# Braille_drive.net
KiCad netlist of a schematic drawn in EAGLE
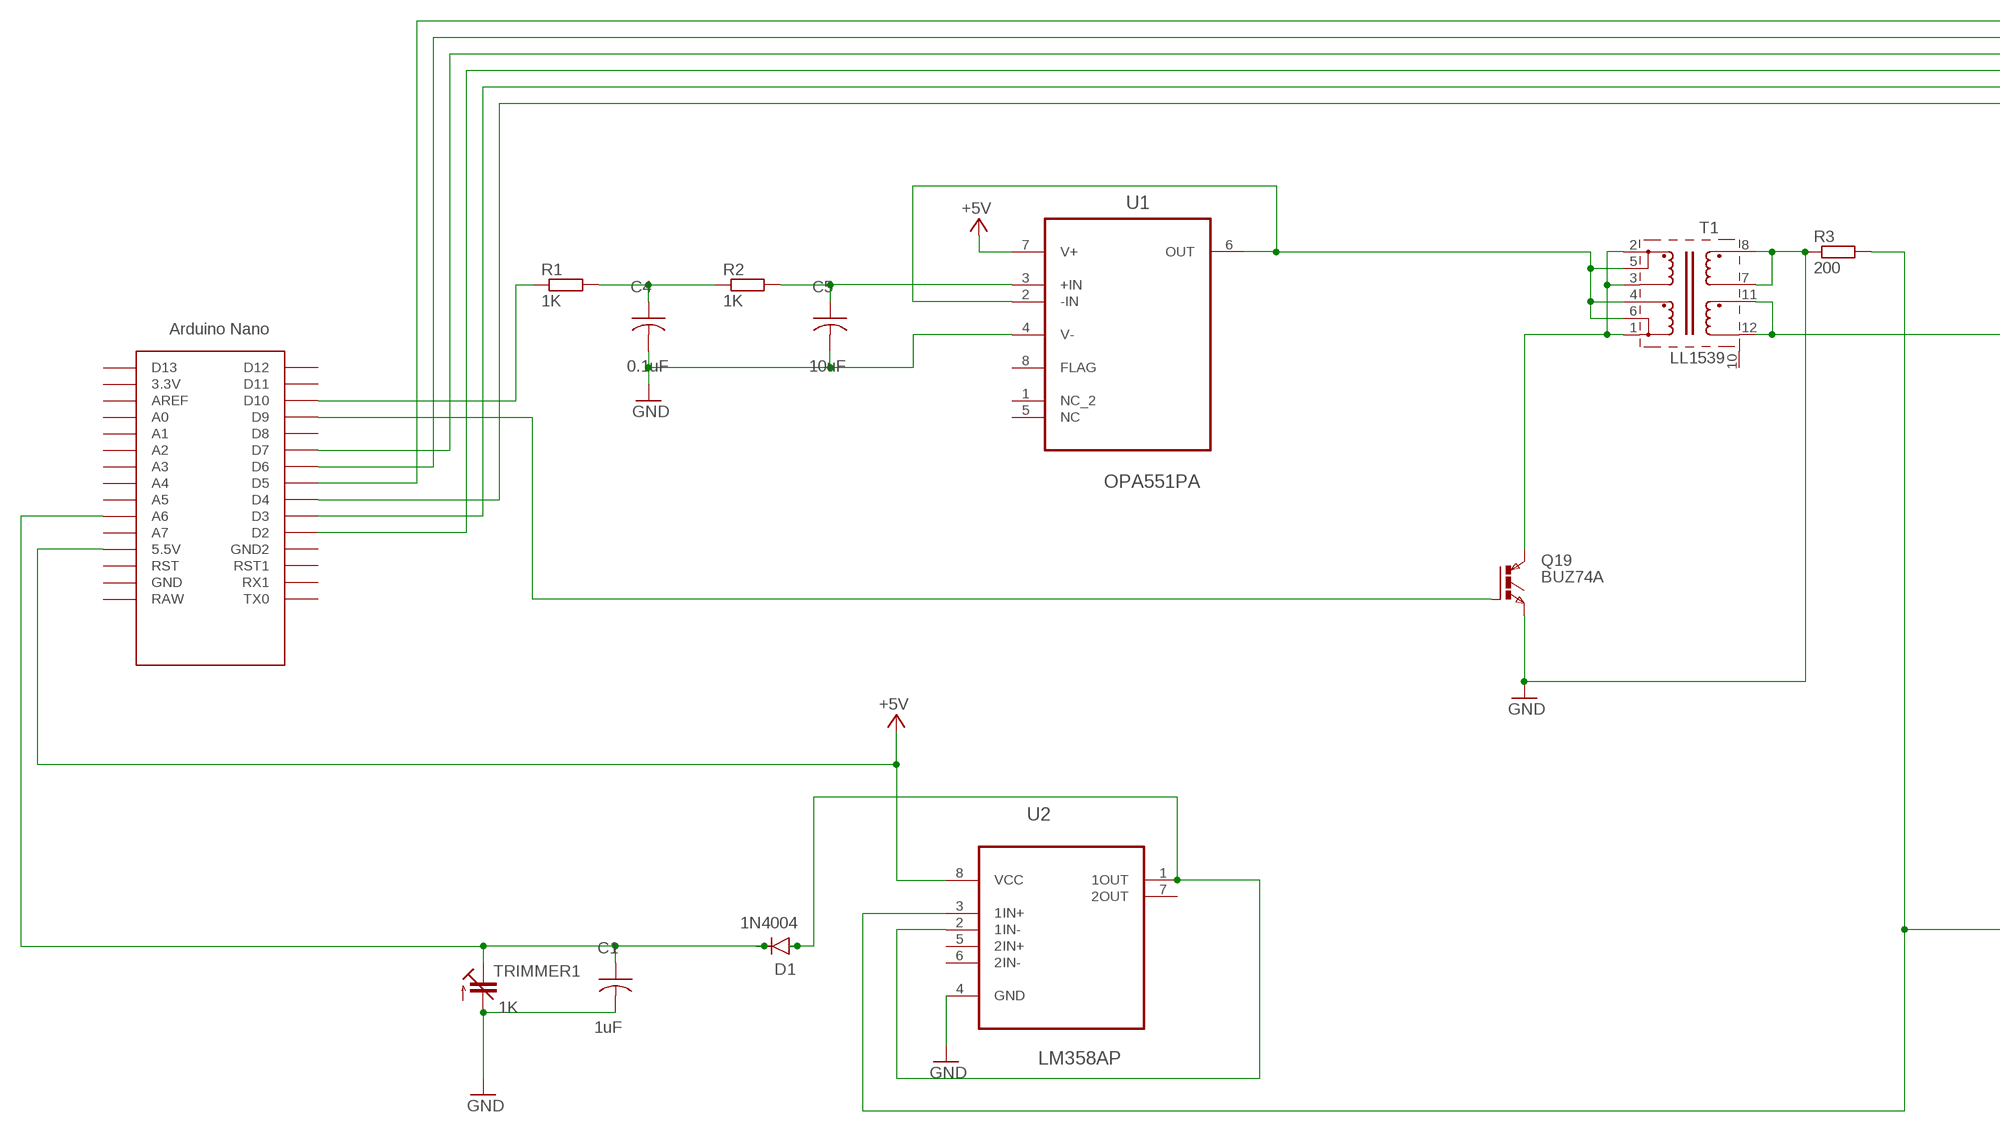
[diagram p0: schematic, sheet 1, part 1 of 2]
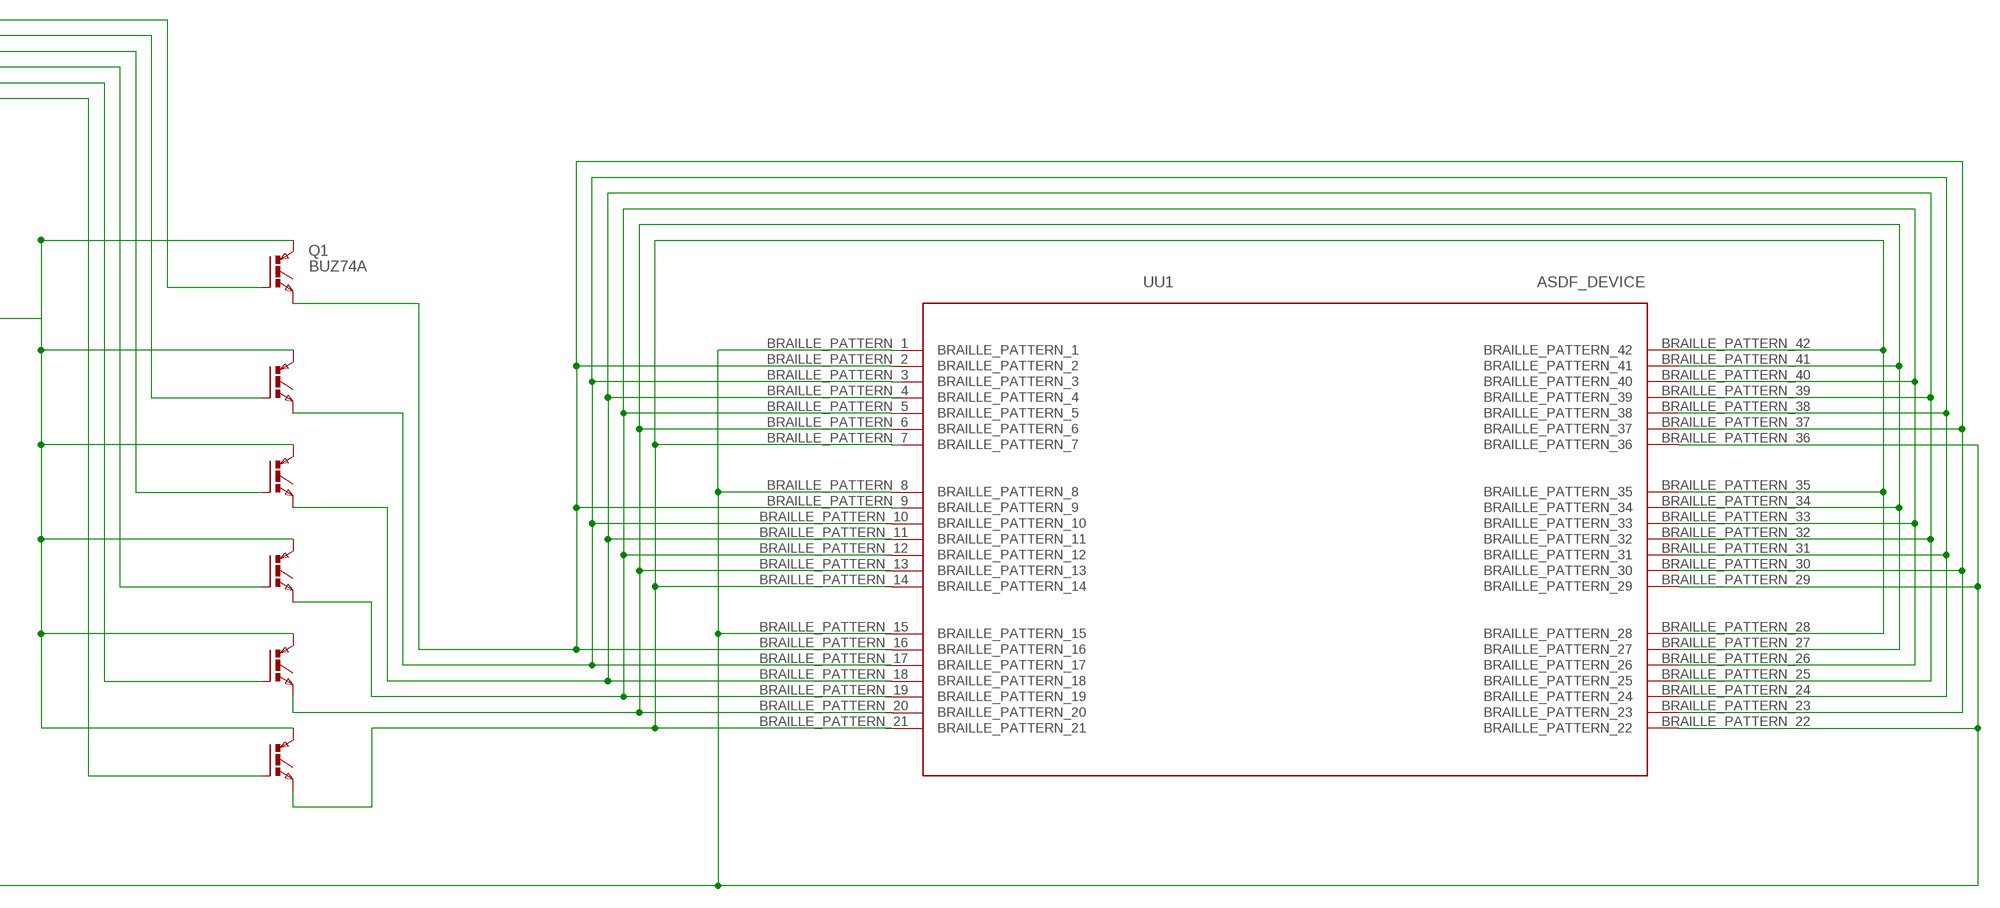
[diagram p1: schematic, sheet 1, part 2 of 2]

(export (version "E")
  (design (tool "Eeschema 10.0.6"))
  (components
    (comp (ref "C1")
      (value "1uF")
      (footprint "eagle-import:CAP_RADIAL_2MM")
      (fields
        (field (name "DIGIKEY_PART_NUMBER") "P5178-ND")
        (field (name "MANUFACTURER") "Panasonic Electronic Components")
        (field (name "MPN") "ECA-1HM100")
        (field (name "CREATED_BY") "PCBLayout.com")
      )
      (libsource (lib "eagle-import") (part "ECA-1HM100"))
    )
    (comp (ref "C4")
      (value "0.1uF")
      (footprint "eagle-import:CAP_RADIAL_2MM")
      (fields
        (field (name "DIGIKEY_PART_NUMBER") "P5178-ND")
        (field (name "MANUFACTURER") "Panasonic Electronic Components")
        (field (name "MPN") "ECA-1HM100")
        (field (name "CREATED_BY") "PCBLayout.com")
      )
      (libsource (lib "eagle-import") (part "ECA-1HM100"))
    )
    (comp (ref "C5")
      (value "10uF")
      (footprint "eagle-import:CAP_RADIAL_2MM")
      (fields
        (field (name "DIGIKEY_PART_NUMBER") "P5178-ND")
        (field (name "MANUFACTURER") "Panasonic Electronic Components")
        (field (name "MPN") "ECA-1HM100")
        (field (name "CREATED_BY") "PCBLayout.com")
      )
      (libsource (lib "eagle-import") (part "ECA-1HM100"))
    )
    (comp (ref "D1")
      (value "1N4004")
      (footprint "eagle-import:DO-41")
      (fields
        (field (name "DIGIKEY_PART_NUMBER") "1N4004MSCT-ND")
        (field (name "MANUFACTURER") "Micro Commercial Co")
        (field (name "CREATED_BY") "PCBLayout.com")
      )
      (libsource (lib "eagle-import") (part "1N4004"))
    )
    (comp (ref "Q1")
      (value "BUZ74A")
      (footprint "eagle-import:TO220AV")
      (libsource (lib "eagle-import") (part "IGBTTO220AV"))
    )
    (comp (ref "Q2")
      (value "BUZ74A")
      (footprint "eagle-import:TO220AV")
      (libsource (lib "eagle-import") (part "IGBTTO220AV"))
    )
    (comp (ref "Q3")
      (value "BUZ74A")
      (footprint "eagle-import:TO220AV")
      (libsource (lib "eagle-import") (part "IGBTTO220AV"))
    )
    (comp (ref "Q4")
      (value "BUZ74A")
      (footprint "eagle-import:TO220AV")
      (libsource (lib "eagle-import") (part "IGBTTO220AV"))
    )
    (comp (ref "Q5")
      (value "BUZ74A")
      (footprint "eagle-import:TO220AV")
      (libsource (lib "eagle-import") (part "IGBTTO220AV"))
    )
    (comp (ref "Q6")
      (value "BUZ74A")
      (footprint "eagle-import:TO220AV")
      (libsource (lib "eagle-import") (part "IGBTTO220AV"))
    )
    (comp (ref "Q19")
      (value "BUZ74A")
      (footprint "eagle-import:TO220AV")
      (libsource (lib "eagle-import") (part "IGBTTO220AV"))
    )
    (comp (ref "R1")
      (value "1K")
      (footprint "eagle-import:0204V")
      (libsource (lib "eagle-import") (part "R-EU_0204/2V"))
    )
    (comp (ref "R2")
      (value "1K")
      (footprint "eagle-import:0204V")
      (libsource (lib "eagle-import") (part "R-EU_0204/2V"))
    )
    (comp (ref "R3")
      (value "200")
      (footprint "eagle-import:0204V")
      (libsource (lib "eagle-import") (part "R-EU_0204/2V"))
    )
    (comp (ref "T1")
      (value "LL1539")
      (footprint "eagle-import:LL1539")
      (libsource (lib "eagle-import") (part "LL1539"))
    )
    (comp (ref "TRIMMER1")
      (value "1K")
      (footprint "eagle-import:CTRIM3040.452")
      (libsource (lib "eagle-import") (part "C-TRIMM3040.452"))
    )
    (comp (ref "U$1")
      (value "NANO")
      (footprint "eagle-import:NANO")
      (libsource (lib "eagle-import") (part "NANO"))
    )
    (comp (ref "U1")
      (value "OPA551PA")
      (footprint "eagle-import:DIP254P762X508-8")
      (libsource (lib "eagle-import") (part "OPA551PA"))
    )
    (comp (ref "U2")
      (value "LM358AP")
      (footprint "eagle-import:DIP254P762X508-8")
      (libsource (lib "eagle-import") (part "LM358AP"))
    )
    (comp (ref "UU1")
      (value "ASDF_DEVICE")
      (footprint "eagle-import:BRAILLE_PATTERN1")
      (libsource (lib "eagle-import") (part "ASDF_DEVICE"))
    )
  )
  (nets
    (net (code "1") (name "+5V") (class "Default")
      (node (ref "U$1") (pin "5V") (pinfunction "5.5V_5V") (pintype "bidirectional"))
      (node (ref "U1") (pin "7") (pinfunction "V+_7") (pintype "power_in"))
      (node (ref "U2") (pin "8") (pinfunction "VCC_8") (pintype "power_in"))
    )
    (net (code "2") (name "GND") (class "Default")
      (node (ref "C1") (pin "2") (pinfunction "2_2") (pintype "passive"))
      (node (ref "C4") (pin "2") (pinfunction "2_2") (pintype "passive"))
      (node (ref "C5") (pin "2") (pinfunction "2_2") (pintype "passive"))
      (node (ref "Q19") (pin "E") (pinfunction "E_E") (pintype "passive"))
      (node (ref "R3") (pin "1") (pinfunction "1_1") (pintype "passive"))
      (node (ref "T1") (pin "7") (pinfunction "7_7") (pintype "passive"))
      (node (ref "T1") (pin "8") (pinfunction "8_8") (pintype "passive"))
      (node (ref "TRIMMER1") (pin "2") (pinfunction "A_2") (pintype "passive"))
      (node (ref "U1") (pin "4") (pinfunction "V-_4") (pintype "power_in"))
      (node (ref "U2") (pin "4") (pinfunction "GND_4") (pintype "passive"))
    )
    (net (code "3") (name "Net-(C4-Pad1)") (class "Default")
      (node (ref "C4") (pin "1") (pinfunction "1_1") (pintype "passive"))
      (node (ref "R1") (pin "2") (pinfunction "2_2") (pintype "passive"))
      (node (ref "R2") (pin "1") (pinfunction "1_1") (pintype "passive"))
    )
    (net (code "4") (name "Net-(Q1-PadC)") (class "Default")
      (node (ref "Q1") (pin "C") (pinfunction "C_C") (pintype "passive"))
      (node (ref "Q2") (pin "C") (pinfunction "C_C") (pintype "passive"))
      (node (ref "Q3") (pin "C") (pinfunction "C_C") (pintype "passive"))
      (node (ref "Q4") (pin "C") (pinfunction "C_C") (pintype "passive"))
      (node (ref "Q5") (pin "C") (pinfunction "C_C") (pintype "passive"))
      (node (ref "Q6") (pin "C") (pinfunction "C_C") (pintype "passive"))
      (node (ref "T1") (pin "11") (pinfunction "11_11") (pintype "passive"))
      (node (ref "T1") (pin "12") (pinfunction "12_12") (pintype "passive"))
    )
    (net (code "5") (name "Net-(Q1-PadE)") (class "Default")
      (node (ref "Q1") (pin "E") (pinfunction "E_E") (pintype "passive"))
      (node (ref "UU1") (pin "BRAILLE_PATTERN_16") (pinfunction "BRAILLE_PATTERN_16_BRAILLE_PATTERN_16") (pintype "bidirectional"))
      (node (ref "UU1") (pin "BRAILLE_PATTERN_2") (pinfunction "BRAILLE_PATTERN_2_BRAILLE_PATTERN_2") (pintype "bidirectional"))
      (node (ref "UU1") (pin "BRAILLE_PATTERN_23") (pinfunction "BRAILLE_PATTERN_23_BRAILLE_PATTERN_23") (pintype "bidirectional"))
      (node (ref "UU1") (pin "BRAILLE_PATTERN_30") (pinfunction "BRAILLE_PATTERN_30_BRAILLE_PATTERN_30") (pintype "bidirectional"))
      (node (ref "UU1") (pin "BRAILLE_PATTERN_37") (pinfunction "BRAILLE_PATTERN_37_BRAILLE_PATTERN_37") (pintype "bidirectional"))
      (node (ref "UU1") (pin "BRAILLE_PATTERN_9") (pinfunction "BRAILLE_PATTERN_9_BRAILLE_PATTERN_9") (pintype "bidirectional"))
    )
    (net (code "6") (name "Net-(Q1-PadG)") (class "Default")
      (node (ref "Q1") (pin "G") (pinfunction "G_G") (pintype "passive"))
      (node (ref "U$1") (pin "D5") (pinfunction "D5_D5") (pintype "bidirectional"))
    )
    (net (code "7") (name "Net-(Q2-PadE)") (class "Default")
      (node (ref "Q2") (pin "E") (pinfunction "E_E") (pintype "passive"))
      (node (ref "UU1") (pin "BRAILLE_PATTERN_10") (pinfunction "BRAILLE_PATTERN_10_BRAILLE_PATTERN_10") (pintype "bidirectional"))
      (node (ref "UU1") (pin "BRAILLE_PATTERN_17") (pinfunction "BRAILLE_PATTERN_17_BRAILLE_PATTERN_17") (pintype "bidirectional"))
      (node (ref "UU1") (pin "BRAILLE_PATTERN_24") (pinfunction "BRAILLE_PATTERN_24_BRAILLE_PATTERN_24") (pintype "bidirectional"))
      (node (ref "UU1") (pin "BRAILLE_PATTERN_3") (pinfunction "BRAILLE_PATTERN_3_BRAILLE_PATTERN_3") (pintype "bidirectional"))
      (node (ref "UU1") (pin "BRAILLE_PATTERN_31") (pinfunction "BRAILLE_PATTERN_31_BRAILLE_PATTERN_31") (pintype "bidirectional"))
      (node (ref "UU1") (pin "BRAILLE_PATTERN_38") (pinfunction "BRAILLE_PATTERN_38_BRAILLE_PATTERN_38") (pintype "bidirectional"))
    )
    (net (code "8") (name "Net-(Q2-PadG)") (class "Default")
      (node (ref "Q2") (pin "G") (pinfunction "G_G") (pintype "passive"))
      (node (ref "U$1") (pin "D6") (pinfunction "D6_D6") (pintype "bidirectional"))
    )
    (net (code "9") (name "Net-(Q3-PadE)") (class "Default")
      (node (ref "Q3") (pin "E") (pinfunction "E_E") (pintype "passive"))
      (node (ref "UU1") (pin "BRAILLE_PATTERN_11") (pinfunction "BRAILLE_PATTERN_11_BRAILLE_PATTERN_11") (pintype "bidirectional"))
      (node (ref "UU1") (pin "BRAILLE_PATTERN_18") (pinfunction "BRAILLE_PATTERN_18_BRAILLE_PATTERN_18") (pintype "bidirectional"))
      (node (ref "UU1") (pin "BRAILLE_PATTERN_25") (pinfunction "BRAILLE_PATTERN_25_BRAILLE_PATTERN_25") (pintype "bidirectional"))
      (node (ref "UU1") (pin "BRAILLE_PATTERN_32") (pinfunction "BRAILLE_PATTERN_32_BRAILLE_PATTERN_32") (pintype "bidirectional"))
      (node (ref "UU1") (pin "BRAILLE_PATTERN_39") (pinfunction "BRAILLE_PATTERN_39_BRAILLE_PATTERN_39") (pintype "bidirectional"))
      (node (ref "UU1") (pin "BRAILLE_PATTERN_4") (pinfunction "BRAILLE_PATTERN_4_BRAILLE_PATTERN_4") (pintype "bidirectional"))
    )
    (net (code "10") (name "Net-(Q3-PadG)") (class "Default")
      (node (ref "Q3") (pin "G") (pinfunction "G_G") (pintype "passive"))
      (node (ref "U$1") (pin "D7") (pinfunction "D7_D7") (pintype "bidirectional"))
    )
    (net (code "11") (name "Net-(Q4-PadE)") (class "Default")
      (node (ref "Q4") (pin "E") (pinfunction "E_E") (pintype "passive"))
      (node (ref "UU1") (pin "BRAILLE_PATTERN_12") (pinfunction "BRAILLE_PATTERN_12_BRAILLE_PATTERN_12") (pintype "bidirectional"))
      (node (ref "UU1") (pin "BRAILLE_PATTERN_19") (pinfunction "BRAILLE_PATTERN_19_BRAILLE_PATTERN_19") (pintype "bidirectional"))
      (node (ref "UU1") (pin "BRAILLE_PATTERN_26") (pinfunction "BRAILLE_PATTERN_26_BRAILLE_PATTERN_26") (pintype "bidirectional"))
      (node (ref "UU1") (pin "BRAILLE_PATTERN_33") (pinfunction "BRAILLE_PATTERN_33_BRAILLE_PATTERN_33") (pintype "bidirectional"))
      (node (ref "UU1") (pin "BRAILLE_PATTERN_40") (pinfunction "BRAILLE_PATTERN_40_BRAILLE_PATTERN_40") (pintype "bidirectional"))
      (node (ref "UU1") (pin "BRAILLE_PATTERN_5") (pinfunction "BRAILLE_PATTERN_5_BRAILLE_PATTERN_5") (pintype "bidirectional"))
    )
    (net (code "12") (name "Net-(Q4-PadG)") (class "Default")
      (node (ref "Q4") (pin "G") (pinfunction "G_G") (pintype "passive"))
      (node (ref "U$1") (pin "D2") (pinfunction "D2_D2") (pintype "bidirectional"))
    )
    (net (code "13") (name "Net-(Q5-PadE)") (class "Default")
      (node (ref "Q5") (pin "E") (pinfunction "E_E") (pintype "passive"))
      (node (ref "UU1") (pin "BRAILLE_PATTERN_13") (pinfunction "BRAILLE_PATTERN_13_BRAILLE_PATTERN_13") (pintype "bidirectional"))
      (node (ref "UU1") (pin "BRAILLE_PATTERN_20") (pinfunction "BRAILLE_PATTERN_20_BRAILLE_PATTERN_20") (pintype "bidirectional"))
      (node (ref "UU1") (pin "BRAILLE_PATTERN_27") (pinfunction "BRAILLE_PATTERN_27_BRAILLE_PATTERN_27") (pintype "bidirectional"))
      (node (ref "UU1") (pin "BRAILLE_PATTERN_34") (pinfunction "BRAILLE_PATTERN_34_BRAILLE_PATTERN_34") (pintype "bidirectional"))
      (node (ref "UU1") (pin "BRAILLE_PATTERN_41") (pinfunction "BRAILLE_PATTERN_41_BRAILLE_PATTERN_41") (pintype "bidirectional"))
      (node (ref "UU1") (pin "BRAILLE_PATTERN_6") (pinfunction "BRAILLE_PATTERN_6_BRAILLE_PATTERN_6") (pintype "bidirectional"))
    )
    (net (code "14") (name "Net-(Q5-PadG)") (class "Default")
      (node (ref "Q5") (pin "G") (pinfunction "G_G") (pintype "passive"))
      (node (ref "U$1") (pin "D3") (pinfunction "D3_D3") (pintype "bidirectional"))
    )
    (net (code "15") (name "Net-(Q6-PadE)") (class "Default")
      (node (ref "Q6") (pin "E") (pinfunction "E_E") (pintype "passive"))
      (node (ref "UU1") (pin "BRAILLE_PATTERN_14") (pinfunction "BRAILLE_PATTERN_14_BRAILLE_PATTERN_14") (pintype "bidirectional"))
      (node (ref "UU1") (pin "BRAILLE_PATTERN_21") (pinfunction "BRAILLE_PATTERN_21_BRAILLE_PATTERN_21") (pintype "bidirectional"))
      (node (ref "UU1") (pin "BRAILLE_PATTERN_28") (pinfunction "BRAILLE_PATTERN_28_BRAILLE_PATTERN_28") (pintype "bidirectional"))
      (node (ref "UU1") (pin "BRAILLE_PATTERN_35") (pinfunction "BRAILLE_PATTERN_35_BRAILLE_PATTERN_35") (pintype "bidirectional"))
      (node (ref "UU1") (pin "BRAILLE_PATTERN_42") (pinfunction "BRAILLE_PATTERN_42_BRAILLE_PATTERN_42") (pintype "bidirectional"))
      (node (ref "UU1") (pin "BRAILLE_PATTERN_7") (pinfunction "BRAILLE_PATTERN_7_BRAILLE_PATTERN_7") (pintype "bidirectional"))
    )
    (net (code "16") (name "Net-(Q6-PadG)") (class "Default")
      (node (ref "Q6") (pin "G") (pinfunction "G_G") (pintype "passive"))
      (node (ref "U$1") (pin "D4") (pinfunction "D4_D4") (pintype "bidirectional"))
    )
    (net (code "17") (name "Net-(Q19-PadC)") (class "Default")
      (node (ref "Q19") (pin "C") (pinfunction "C_C") (pintype "passive"))
      (node (ref "T1") (pin "1") (pinfunction "1_1") (pintype "passive"))
      (node (ref "T1") (pin "2") (pinfunction "2_2") (pintype "passive"))
      (node (ref "T1") (pin "3") (pinfunction "3_3") (pintype "passive"))
    )
    (net (code "18") (name "Net-(Q19-PadG)") (class "Default")
      (node (ref "Q19") (pin "G") (pinfunction "G_G") (pintype "passive"))
      (node (ref "U$1") (pin "D9") (pinfunction "D9_D9") (pintype "bidirectional"))
    )
    (net (code "19") (name "Net-(R1-Pad1)") (class "Default")
      (node (ref "R1") (pin "1") (pinfunction "1_1") (pintype "passive"))
      (node (ref "U$1") (pin "D10") (pinfunction "D10_D10") (pintype "bidirectional"))
    )
    (net (code "20") (name "Net-(TRIMMER1-E)") (class "Default")
      (node (ref "C1") (pin "1") (pinfunction "1_1") (pintype "passive"))
      (node (ref "D1") (pin "C") (pinfunction "C_C") (pintype "passive"))
      (node (ref "TRIMMER1") (pin "1A") (pinfunction "E_1A") (pintype "passive"))
      (node (ref "U$1") (pin "A6") (pinfunction "A6_A6") (pintype "bidirectional"))
    )
    (net (code "21") (name "Net-(U1-+IN)") (class "Default")
      (node (ref "C5") (pin "1") (pinfunction "1_1") (pintype "passive"))
      (node (ref "R2") (pin "2") (pinfunction "2_2") (pintype "passive"))
      (node (ref "U1") (pin "3") (pinfunction "+IN_3") (pintype "input"))
    )
    (net (code "22") (name "Net-(U1--IN)") (class "Default")
      (node (ref "T1") (pin "4") (pinfunction "4_4") (pintype "passive"))
      (node (ref "T1") (pin "5") (pinfunction "5_5") (pintype "passive"))
      (node (ref "T1") (pin "6") (pinfunction "6_6") (pintype "passive"))
      (node (ref "U1") (pin "2") (pinfunction "-IN_2") (pintype "input"))
      (node (ref "U1") (pin "6") (pinfunction "OUT_6") (pintype "output"))
    )
    (net (code "23") (name "Net-(U2-1IN+)") (class "Default")
      (node (ref "R3") (pin "2") (pinfunction "2_2") (pintype "passive"))
      (node (ref "U2") (pin "3") (pinfunction "1IN+_3") (pintype "input"))
      (node (ref "UU1") (pin "BRAILLE_PATTERN_1") (pinfunction "BRAILLE_PATTERN_1_BRAILLE_PATTERN_1") (pintype "bidirectional"))
      (node (ref "UU1") (pin "BRAILLE_PATTERN_15") (pinfunction "BRAILLE_PATTERN_15_BRAILLE_PATTERN_15") (pintype "bidirectional"))
      (node (ref "UU1") (pin "BRAILLE_PATTERN_22") (pinfunction "BRAILLE_PATTERN_22_BRAILLE_PATTERN_22") (pintype "bidirectional"))
      (node (ref "UU1") (pin "BRAILLE_PATTERN_29") (pinfunction "BRAILLE_PATTERN_29_BRAILLE_PATTERN_29") (pintype "bidirectional"))
      (node (ref "UU1") (pin "BRAILLE_PATTERN_36") (pinfunction "BRAILLE_PATTERN_36_BRAILLE_PATTERN_36") (pintype "bidirectional"))
      (node (ref "UU1") (pin "BRAILLE_PATTERN_8") (pinfunction "BRAILLE_PATTERN_8_BRAILLE_PATTERN_8") (pintype "bidirectional"))
    )
    (net (code "24") (name "Net-(U2-1IN-)") (class "Default")
      (node (ref "D1") (pin "A") (pinfunction "A_A") (pintype "passive"))
      (node (ref "U2") (pin "1") (pinfunction "1OUT_1") (pintype "output"))
      (node (ref "U2") (pin "2") (pinfunction "1IN-_2") (pintype "input"))
    )
    (net (code "25") (name "unconnected-(T1-Pad10)") (class "Default")
      (node (ref "T1") (pin "10") (pinfunction "10_10") (pintype "passive"))
    )
    (net (code "26") (name "unconnected-(U$1-GND2-PadGND1)") (class "Default")
      (node (ref "U$1") (pin "GND1") (pinfunction "GND2_GND1") (pintype "bidirectional"))
    )
    (net (code "27") (name "unconnected-(U$1-Pad3.3V)") (class "Default")
      (node (ref "U$1") (pin "3.3V") (pinfunction "3.3V_3.3V") (pintype "bidirectional"))
    )
    (net (code "28") (name "unconnected-(U$1-PadA0)") (class "Default")
      (node (ref "U$1") (pin "A0") (pinfunction "A0_A0") (pintype "bidirectional"))
    )
    (net (code "29") (name "unconnected-(U$1-PadA1)") (class "Default")
      (node (ref "U$1") (pin "A1") (pinfunction "A1_A1") (pintype "bidirectional"))
    )
    (net (code "30") (name "unconnected-(U$1-PadA2)") (class "Default")
      (node (ref "U$1") (pin "A2") (pinfunction "A2_A2") (pintype "bidirectional"))
    )
    (net (code "31") (name "unconnected-(U$1-PadA3)") (class "Default")
      (node (ref "U$1") (pin "A3") (pinfunction "A3_A3") (pintype "bidirectional"))
    )
    (net (code "32") (name "unconnected-(U$1-PadA4)") (class "Default")
      (node (ref "U$1") (pin "A4") (pinfunction "A4_A4") (pintype "bidirectional"))
    )
    (net (code "33") (name "unconnected-(U$1-PadA5)") (class "Default")
      (node (ref "U$1") (pin "A5") (pinfunction "A5_A5") (pintype "bidirectional"))
    )
    (net (code "34") (name "unconnected-(U$1-PadA7)") (class "Default")
      (node (ref "U$1") (pin "A7") (pinfunction "A7_A7") (pintype "bidirectional"))
    )
    (net (code "35") (name "unconnected-(U$1-PadAREF)") (class "Default")
      (node (ref "U$1") (pin "AREF") (pinfunction "AREF_AREF") (pintype "bidirectional"))
    )
    (net (code "36") (name "unconnected-(U$1-PadD8)") (class "Default")
      (node (ref "U$1") (pin "D8") (pinfunction "D8_D8") (pintype "bidirectional"))
    )
    (net (code "37") (name "unconnected-(U$1-PadD11)") (class "Default")
      (node (ref "U$1") (pin "D11") (pinfunction "D11_D11") (pintype "bidirectional"))
    )
    (net (code "38") (name "unconnected-(U$1-PadD12)") (class "Default")
      (node (ref "U$1") (pin "D12") (pinfunction "D12_D12") (pintype "bidirectional"))
    )
    (net (code "39") (name "unconnected-(U$1-PadD13)") (class "Default")
      (node (ref "U$1") (pin "D13") (pinfunction "D13_D13") (pintype "bidirectional"))
    )
    (net (code "40") (name "unconnected-(U$1-PadGND)") (class "Default")
      (node (ref "U$1") (pin "GND") (pinfunction "GND_GND") (pintype "bidirectional"))
    )
    (net (code "41") (name "unconnected-(U$1-PadICSP1)") (class "Default")
      (node (ref "U$1") (pin "ICSP1") (pinfunction "ICSP1_ICSP1") (pintype "bidirectional"))
    )
    (net (code "42") (name "unconnected-(U$1-PadICSP2)") (class "Default")
      (node (ref "U$1") (pin "ICSP2") (pinfunction "ICSP2_ICSP2") (pintype "bidirectional"))
    )
    (net (code "43") (name "unconnected-(U$1-PadICSP3)") (class "Default")
      (node (ref "U$1") (pin "ICSP3") (pinfunction "ICSP3_ICSP3") (pintype "bidirectional"))
    )
    (net (code "44") (name "unconnected-(U$1-PadICSP4)") (class "Default")
      (node (ref "U$1") (pin "ICSP4") (pinfunction "ICSP4_ICSP4") (pintype "bidirectional"))
    )
    (net (code "45") (name "unconnected-(U$1-PadICSP5)") (class "Default")
      (node (ref "U$1") (pin "ICSP5") (pinfunction "ICSP5_ICSP5") (pintype "bidirectional"))
    )
    (net (code "46") (name "unconnected-(U$1-PadICSP6)") (class "Default")
      (node (ref "U$1") (pin "ICSP6") (pinfunction "ICSP6_ICSP6") (pintype "bidirectional"))
    )
    (net (code "47") (name "unconnected-(U$1-PadRAW)") (class "Default")
      (node (ref "U$1") (pin "RAW") (pinfunction "RAW_RAW") (pintype "bidirectional"))
    )
    (net (code "48") (name "unconnected-(U$1-PadRST)") (class "Default")
      (node (ref "U$1") (pin "RST") (pinfunction "RST_RST") (pintype "bidirectional"))
    )
    (net (code "49") (name "unconnected-(U$1-PadRST1)") (class "Default")
      (node (ref "U$1") (pin "RST1") (pinfunction "RST1_RST1") (pintype "bidirectional"))
    )
    (net (code "50") (name "unconnected-(U$1-PadRX1)") (class "Default")
      (node (ref "U$1") (pin "RX1") (pinfunction "RX1_RX1") (pintype "bidirectional"))
    )
    (net (code "51") (name "unconnected-(U$1-PadTX0)") (class "Default")
      (node (ref "U$1") (pin "TX0") (pinfunction "TX0_TX0") (pintype "bidirectional"))
    )
    (net (code "52") (name "unconnected-(U1-FLAG-Pad8)") (class "Default")
      (node (ref "U1") (pin "8") (pinfunction "FLAG_8") (pintype "passive"))
    )
    (net (code "53") (name "unconnected-(U1-NC-Pad5)") (class "Default")
      (node (ref "U1") (pin "5") (pinfunction "NC_5") (pintype "no_connect"))
    )
    (net (code "54") (name "unconnected-(U1-NC_2-Pad1)") (class "Default")
      (node (ref "U1") (pin "1") (pinfunction "NC_2_1") (pintype "no_connect"))
    )
    (net (code "55") (name "unconnected-(U2-2IN+-Pad5)") (class "Default")
      (node (ref "U2") (pin "5") (pinfunction "2IN+_5") (pintype "input"))
    )
    (net (code "56") (name "unconnected-(U2-2IN--Pad6)") (class "Default")
      (node (ref "U2") (pin "6") (pinfunction "2IN-_6") (pintype "input"))
    )
    (net (code "57") (name "unconnected-(U2-2OUT-Pad7)") (class "Default")
      (node (ref "U2") (pin "7") (pinfunction "2OUT_7") (pintype "output"))
    )
  )
)
